# picstick_27j53_v1.net
KiCad netlist of a schematic drawn in EAGLE
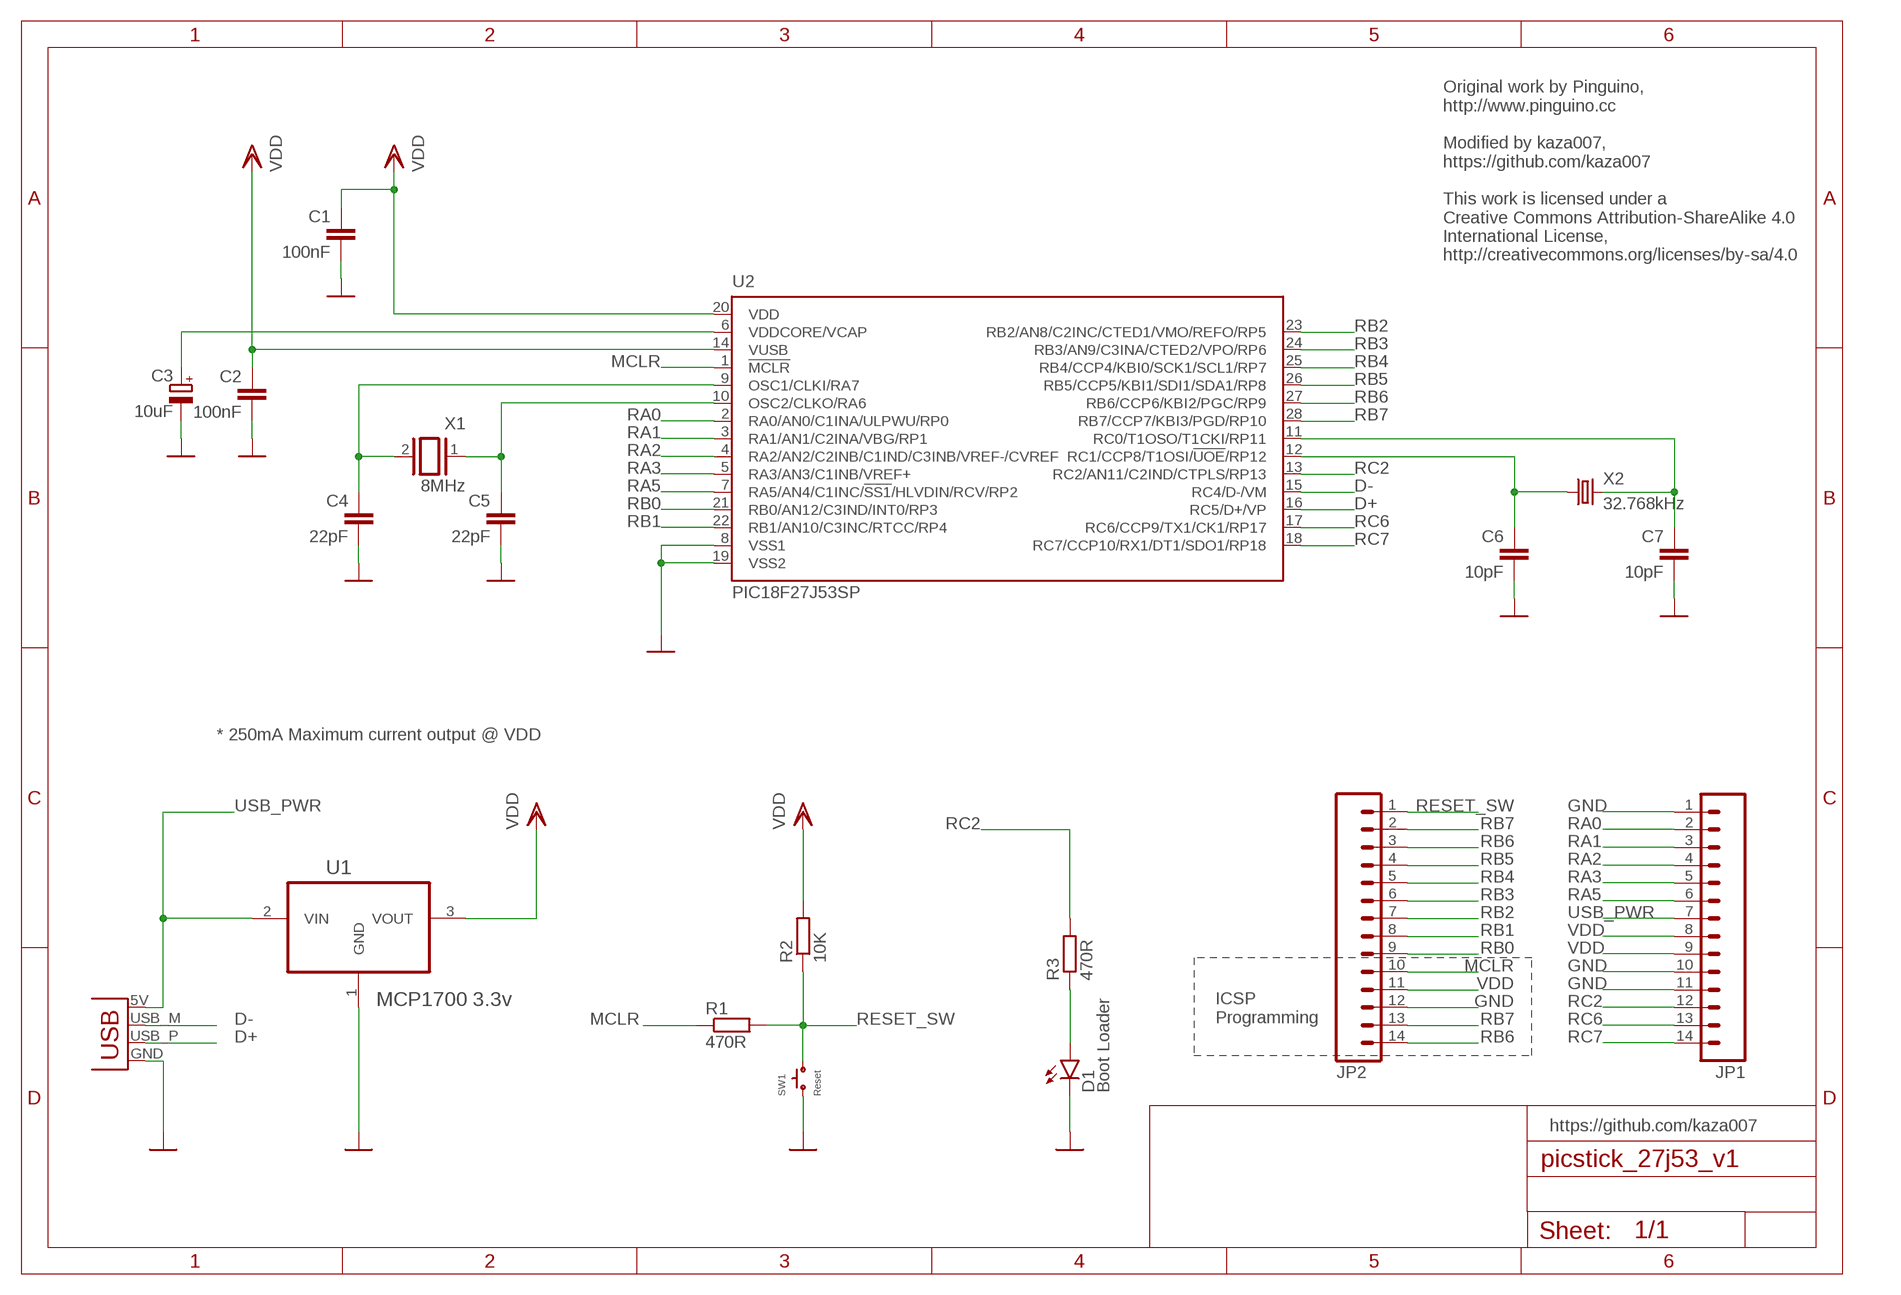
[diagram p0: schematic, sheet 1]

(export (version "E")
  (design (tool "Eeschema 10.0.6"))
  (components
    (comp (ref "C1")
      (value "100nF")
      (footprint "eagle-import:C050-024X044")
      (libsource (lib "eagle-import") (part "C-EU050-024X044"))
    )
    (comp (ref "C2")
      (value "100nF")
      (footprint "eagle-import:C050-024X044")
      (libsource (lib "eagle-import") (part "C-EU050-024X044"))
    )
    (comp (ref "C3")
      (value "10uF")
      (footprint "eagle-import:E2,5-5")
      (libsource (lib "eagle-import") (part "CPOL-EUE2.5-5"))
    )
    (comp (ref "C4")
      (value "22pF")
      (footprint "eagle-import:C025-024X044")
      (libsource (lib "eagle-import") (part "C-EU025-024X044"))
    )
    (comp (ref "C5")
      (value "22pF")
      (footprint "eagle-import:C025-024X044")
      (libsource (lib "eagle-import") (part "C-EU025-024X044"))
    )
    (comp (ref "C6")
      (value "10pF")
      (footprint "eagle-import:C025-024X044")
      (libsource (lib "eagle-import") (part "C-EU025-024X044"))
    )
    (comp (ref "C7")
      (value "10pF")
      (footprint "eagle-import:C025-024X044")
      (libsource (lib "eagle-import") (part "C-EU025-024X044"))
    )
    (comp (ref "D1")
      (value "Boot Loader")
      (footprint "eagle-import:LED3MM")
      (libsource (lib "eagle-import") (part "LED3MM"))
    )
    (comp (ref "JP1")
      (value "FREETRONICS-JON_M14")
      (footprint "eagle-import:FREETRONICS-JON_1X14")
      (libsource (lib "eagle-import") (part "FREETRONICS-JON_M14"))
    )
    (comp (ref "JP2")
      (value "FREETRONICS-JON_M14")
      (footprint "eagle-import:FREETRONICS-JON_1X14")
      (libsource (lib "eagle-import") (part "FREETRONICS-JON_M14"))
    )
    (comp (ref "R1")
      (value "470R")
      (footprint "eagle-import:0204_7")
      (libsource (lib "eagle-import") (part "R-EU_0204/7"))
    )
    (comp (ref "R2")
      (value "10K")
      (footprint "eagle-import:0204_7")
      (libsource (lib "eagle-import") (part "R-EU_0204/7"))
    )
    (comp (ref "R3")
      (value "470R")
      (footprint "eagle-import:0204_7")
      (libsource (lib "eagle-import") (part "R-EU_0204/7"))
    )
    (comp (ref "SW1")
      (value "Reset")
      (footprint "eagle-import:SKHLAAA010")
      (libsource (lib "eagle-import") (part "SKHLAAA010"))
    )
    (comp (ref "U1")
      (value "MCP1700 3.3v")
      (footprint "eagle-import:TO127P254X495-3")
      (fields (field (name "MPN") "MCP1700-3302E/TO"))
      (libsource (lib "eagle-import") (part "MCP1700-3302E/TO"))
    )
    (comp (ref "U2")
      (value "PIC18F27J53SP")
      (footprint "eagle-import:DIL28-3")
      (fields (field (name "MPN") "PIC18F27J53-I/SP"))
      (libsource (lib "eagle-import") (part "PIC18F2J53SP7"))
    )
    (comp (ref "USB")
      (value "FREETRONICS-MASTER-V1_USBPCB")
      (footprint "eagle-import:FREETRONICS-MASTER-V1_USB-A-PCB")
      (libsource (lib "eagle-import") (part "FREETRONICS-MASTER-V1_USBPCB"))
    )
    (comp (ref "X1")
      (value "8MHz")
      (footprint "eagle-import:QS")
      (libsource (lib "eagle-import") (part "XTAL/S"))
    )
    (comp (ref "X2")
      (value "32.768kHz")
      (footprint "eagle-import:TC26H")
      (libsource (lib "eagle-import") (part "CRYSTALTC26H"))
    )
  )
  (nets
    (net (code "1") (name "/D+") (class "Default")
      (node (ref "U2") (pin "16") (pinfunction "RC5/D+/VP_16") (pintype "bidirectional"))
      (node (ref "USB") (pin "USB_P") (pinfunction "D+_USB_P") (pintype "bidirectional"))
    )
    (net (code "2") (name "/D-") (class "Default")
      (node (ref "U2") (pin "15") (pinfunction "RC4/D-/VM_15") (pintype "bidirectional"))
      (node (ref "USB") (pin "USB_M") (pinfunction "D-_USB_M") (pintype "bidirectional"))
    )
    (net (code "3") (name "/MCLR") (class "Default")
      (node (ref "JP2") (pin "10") (pinfunction "10_10") (pintype "passive"))
      (node (ref "R1") (pin "1") (pinfunction "1_1") (pintype "passive"))
      (node (ref "U2") (pin "1") (pinfunction "~{MCLR}_1") (pintype "input"))
    )
    (net (code "4") (name "/RA0") (class "Default")
      (node (ref "JP1") (pin "2") (pinfunction "2_2") (pintype "passive"))
      (node (ref "U2") (pin "2") (pinfunction "RA0/AN0/C1INA/ULPWU/RP0_2") (pintype "bidirectional"))
    )
    (net (code "5") (name "/RA1") (class "Default")
      (node (ref "JP1") (pin "3") (pinfunction "3_3") (pintype "passive"))
      (node (ref "U2") (pin "3") (pinfunction "RA1/AN1/C2INA/VBG/RP1_3") (pintype "bidirectional"))
    )
    (net (code "6") (name "/RA2") (class "Default")
      (node (ref "JP1") (pin "4") (pinfunction "4_4") (pintype "passive"))
      (node (ref "U2") (pin "4") (pinfunction "RA2/AN2/C2INB/C1IND/C3INB/VREF-/CVREF_4") (pintype "bidirectional"))
    )
    (net (code "7") (name "/RA3") (class "Default")
      (node (ref "JP1") (pin "5") (pinfunction "5_5") (pintype "passive"))
      (node (ref "U2") (pin "5") (pinfunction "RA3/AN3/C1INB/VREF+_5") (pintype "bidirectional"))
    )
    (net (code "8") (name "/RA5") (class "Default")
      (node (ref "JP1") (pin "6") (pinfunction "6_6") (pintype "passive"))
      (node (ref "U2") (pin "7") (pinfunction "RA5/AN4/C1INC/~{SS1}/HLVDIN/RCV/RP2_7") (pintype "bidirectional"))
    )
    (net (code "9") (name "/RB0") (class "Default")
      (node (ref "JP2") (pin "9") (pinfunction "9_9") (pintype "passive"))
      (node (ref "U2") (pin "21") (pinfunction "RB0/AN12/C3IND/INT0/RP3_21") (pintype "bidirectional"))
    )
    (net (code "10") (name "/RB1") (class "Default")
      (node (ref "JP2") (pin "8") (pinfunction "8_8") (pintype "passive"))
      (node (ref "U2") (pin "22") (pinfunction "RB1/AN10/C3INC/RTCC/RP4_22") (pintype "bidirectional"))
    )
    (net (code "11") (name "/RB2") (class "Default")
      (node (ref "JP2") (pin "7") (pinfunction "7_7") (pintype "passive"))
      (node (ref "U2") (pin "23") (pinfunction "RB2/AN8/C2INC/CTED1/VMO/REFO/RP5_23") (pintype "bidirectional"))
    )
    (net (code "12") (name "/RB3") (class "Default")
      (node (ref "JP2") (pin "6") (pinfunction "6_6") (pintype "passive"))
      (node (ref "U2") (pin "24") (pinfunction "RB3/AN9/C3INA/CTED2/VPO/RP6_24") (pintype "bidirectional"))
    )
    (net (code "13") (name "/RB4") (class "Default")
      (node (ref "JP2") (pin "5") (pinfunction "5_5") (pintype "passive"))
      (node (ref "U2") (pin "25") (pinfunction "RB4/CCP4/KBI0/SCK1/SCL1/RP7_25") (pintype "bidirectional"))
    )
    (net (code "14") (name "/RB5") (class "Default")
      (node (ref "JP2") (pin "4") (pinfunction "4_4") (pintype "passive"))
      (node (ref "U2") (pin "26") (pinfunction "RB5/CCP5/KBI1/SDI1/SDA1/RP8_26") (pintype "bidirectional"))
    )
    (net (code "15") (name "/RB6") (class "Default")
      (node (ref "JP2") (pin "14") (pinfunction "14_14") (pintype "passive"))
      (node (ref "JP2") (pin "3") (pinfunction "3_3") (pintype "passive"))
      (node (ref "U2") (pin "27") (pinfunction "RB6/CCP6/KBI2/PGC/RP9_27") (pintype "bidirectional"))
    )
    (net (code "16") (name "/RB7") (class "Default")
      (node (ref "JP2") (pin "13") (pinfunction "13_13") (pintype "passive"))
      (node (ref "JP2") (pin "2") (pinfunction "2_2") (pintype "passive"))
      (node (ref "U2") (pin "28") (pinfunction "RB7/CCP7/KBI3/PGD/RP10_28") (pintype "bidirectional"))
    )
    (net (code "17") (name "/RC2") (class "Default")
      (node (ref "JP1") (pin "12") (pinfunction "12_12") (pintype "passive"))
      (node (ref "R3") (pin "2") (pinfunction "2_2") (pintype "passive"))
      (node (ref "U2") (pin "13") (pinfunction "RC2/AN11/C2IND/CTPLS/RP13_13") (pintype "bidirectional"))
    )
    (net (code "18") (name "/RC6") (class "Default")
      (node (ref "JP1") (pin "13") (pinfunction "13_13") (pintype "passive"))
      (node (ref "U2") (pin "17") (pinfunction "RC6/CCP9/TX1/CK1/RP17_17") (pintype "bidirectional"))
    )
    (net (code "19") (name "/RC7") (class "Default")
      (node (ref "JP1") (pin "14") (pinfunction "14_14") (pintype "passive"))
      (node (ref "U2") (pin "18") (pinfunction "RC7/CCP10/RX1/DT1/SDO1/RP18_18") (pintype "bidirectional"))
    )
    (net (code "20") (name "/RESET_SW") (class "Default")
      (node (ref "JP2") (pin "1") (pinfunction "1_1") (pintype "passive"))
      (node (ref "R1") (pin "2") (pinfunction "2_2") (pintype "passive"))
      (node (ref "R2") (pin "1") (pinfunction "1_1") (pintype "passive"))
      (node (ref "SW1") (pin "2") (pinfunction "2_2") (pintype "bidirectional"))
    )
    (net (code "21") (name "/USB_PWR") (class "Default")
      (node (ref "JP1") (pin "7") (pinfunction "7_7") (pintype "passive"))
      (node (ref "U1") (pin "2") (pinfunction "VIN_2") (pintype "input"))
      (node (ref "USB") (pin "5V") (pinfunction "VBUS_5V") (pintype "bidirectional"))
    )
    (net (code "22") (name "Net-(D1-PadA)") (class "Default")
      (node (ref "D1") (pin "A") (pinfunction "A_A") (pintype "passive"))
      (node (ref "R3") (pin "1") (pinfunction "1_1") (pintype "passive"))
    )
    (net (code "23") (name "Net-(U2-OSC1{slash}CLKI{slash}RA7)") (class "Default")
      (node (ref "C4") (pin "1") (pinfunction "1_1") (pintype "passive"))
      (node (ref "U2") (pin "9") (pinfunction "OSC1/CLKI/RA7_9") (pintype "bidirectional"))
      (node (ref "X1") (pin "2") (pinfunction "2_2") (pintype "passive"))
    )
    (net (code "24") (name "Net-(U2-OSC2{slash}CLKO{slash}RA6)") (class "Default")
      (node (ref "C5") (pin "1") (pinfunction "1_1") (pintype "passive"))
      (node (ref "U2") (pin "10") (pinfunction "OSC2/CLKO/RA6_10") (pintype "bidirectional"))
      (node (ref "X1") (pin "1") (pinfunction "1_1") (pintype "passive"))
    )
    (net (code "25") (name "Net-(U2-RC0{slash}T1OSO{slash}T1CKI{slash}RP11)") (class "Default")
      (node (ref "C7") (pin "1") (pinfunction "1_1") (pintype "passive"))
      (node (ref "U2") (pin "11") (pinfunction "RC0/T1OSO/T1CKI/RP11_11") (pintype "bidirectional"))
      (node (ref "X2") (pin "2") (pinfunction "2_2") (pintype "passive"))
    )
    (net (code "26") (name "Net-(U2-RC1{slash}CCP8{slash}T1OSI{slash}~{UOE}{slash}RP12)") (class "Default")
      (node (ref "C6") (pin "1") (pinfunction "1_1") (pintype "passive"))
      (node (ref "U2") (pin "12") (pinfunction "RC1/CCP8/T1OSI/~{UOE}/RP12_12") (pintype "bidirectional"))
      (node (ref "X2") (pin "1") (pinfunction "1_1") (pintype "passive"))
    )
    (net (code "27") (name "Net-(U2-VDDCORE{slash}VCAP)") (class "Default")
      (node (ref "C3") (pin "+") (pinfunction "+_+") (pintype "passive"))
      (node (ref "U2") (pin "6") (pinfunction "VDDCORE/VCAP_6") (pintype "input"))
    )
    (net (code "28") (name "SUPPLY1_GND") (class "Default")
      (node (ref "C1") (pin "2") (pinfunction "2_2") (pintype "passive"))
      (node (ref "C2") (pin "2") (pinfunction "2_2") (pintype "passive"))
      (node (ref "C3") (pin "-") (pinfunction "-_-") (pintype "passive"))
      (node (ref "C4") (pin "2") (pinfunction "2_2") (pintype "passive"))
      (node (ref "C5") (pin "2") (pinfunction "2_2") (pintype "passive"))
      (node (ref "C6") (pin "2") (pinfunction "2_2") (pintype "passive"))
      (node (ref "C7") (pin "2") (pinfunction "2_2") (pintype "passive"))
      (node (ref "D1") (pin "K") (pinfunction "C_K") (pintype "passive"))
      (node (ref "JP1") (pin "1") (pinfunction "1_1") (pintype "passive"))
      (node (ref "JP1") (pin "10") (pinfunction "10_10") (pintype "passive"))
      (node (ref "JP1") (pin "11") (pinfunction "11_11") (pintype "passive"))
      (node (ref "JP2") (pin "12") (pinfunction "12_12") (pintype "passive"))
      (node (ref "SW1") (pin "1") (pinfunction "1_1") (pintype "bidirectional"))
      (node (ref "U1") (pin "1") (pinfunction "GND_1") (pintype "passive"))
      (node (ref "U2") (pin "19") (pinfunction "VSS2_19") (pintype "input"))
      (node (ref "U2") (pin "8") (pinfunction "VSS1_8") (pintype "input"))
      (node (ref "USB") (pin "GND") (pinfunction "GND_GND") (pintype "bidirectional"))
    )
    (net (code "29") (name "VDD") (class "Default")
      (node (ref "C1") (pin "1") (pinfunction "1_1") (pintype "passive"))
      (node (ref "C2") (pin "1") (pinfunction "1_1") (pintype "passive"))
      (node (ref "JP1") (pin "8") (pinfunction "8_8") (pintype "passive"))
      (node (ref "JP1") (pin "9") (pinfunction "9_9") (pintype "passive"))
      (node (ref "JP2") (pin "11") (pinfunction "11_11") (pintype "passive"))
      (node (ref "R2") (pin "2") (pinfunction "2_2") (pintype "passive"))
      (node (ref "U1") (pin "3") (pinfunction "VOUT_3") (pintype "output"))
      (node (ref "U2") (pin "14") (pinfunction "VUSB_14") (pintype "input"))
      (node (ref "U2") (pin "20") (pinfunction "VDD_20") (pintype "input"))
    )
  )
)
